# fan.net
KiCad netlist of a schematic drawn in EAGLE
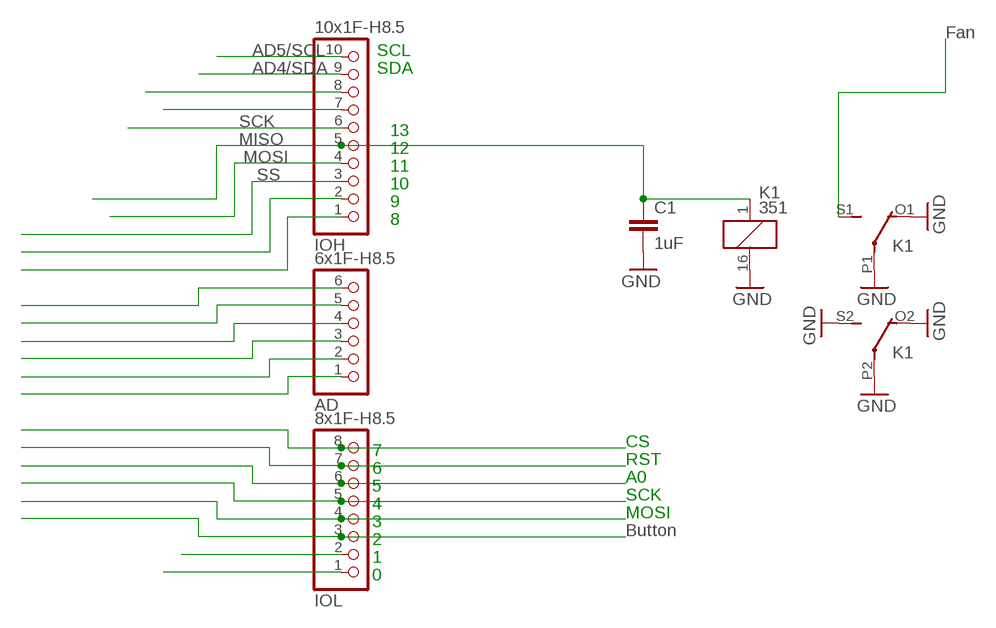
[diagram p0: schematic, sheet 1]

(export (version "E")
  (design (tool "Eeschema 10.0.6"))
  (components
    (comp (ref "AD")
      (value "6x1F-H8.5")
      (footprint "eagle-import:1X06")
      (libsource (lib "eagle-import") (part "PINHD-1X6"))
    )
    (comp (ref "C1")
      (value "1uF")
      (footprint "eagle-import:C2.5-3")
      (libsource (lib "eagle-import") (part "C2,5-3"))
    )
    (comp (ref "IOH")
      (value "10x1F-H8.5")
      (footprint "eagle-import:1X10")
      (libsource (lib "eagle-import") (part "PINHD-1X10_ARD"))
    )
    (comp (ref "IOL")
      (value "8x1F-H8.5")
      (footprint "eagle-import:1X08")
      (libsource (lib "eagle-import") (part "PINHD-1X8"))
    )
    (comp (ref "K1")
      (value "351")
      (footprint "eagle-import:351")
      (libsource (lib "eagle-import") (part "351"))
    )
  )
  (nets
    (net (code "1") (name "/AD4{slash}SDA") (class "Default")
      (node (ref "AD") (pin "5") (pinfunction "5_5") (pintype "passive"))
      (node (ref "IOH") (pin "9") (pinfunction "9_9") (pintype "passive"))
    )
    (net (code "2") (name "/AD5{slash}SCL") (class "Default")
      (node (ref "AD") (pin "6") (pinfunction "6_6") (pintype "passive"))
      (node (ref "IOH") (pin "10") (pinfunction "10_10") (pintype "passive"))
    )
    (net (code "3") (name "/MISO") (class "Default")
      (node (ref "C1") (pin "1") (pinfunction "1_1") (pintype "passive"))
      (node (ref "IOH") (pin "5") (pinfunction "5_5") (pintype "passive"))
      (node (ref "K1") (pin "1") (pinfunction "1_1") (pintype "passive"))
    )
    (net (code "4") (name "/MOSI") (class "Default")
      (node (ref "IOH") (pin "4") (pinfunction "4_4") (pintype "passive"))
    )
    (net (code "5") (name "/SCK") (class "Default")
      (node (ref "IOH") (pin "6") (pinfunction "6_6") (pintype "passive"))
    )
    (net (code "6") (name "/SS") (class "Default")
      (node (ref "IOH") (pin "3") (pinfunction "3_3") (pintype "passive"))
    )
    (net (code "7") (name "GND") (class "Default")
      (node (ref "C1") (pin "2") (pinfunction "2_2") (pintype "passive"))
      (node (ref "IOH") (pin "7") (pinfunction "7_7") (pintype "passive"))
      (node (ref "K1") (pin "16") (pinfunction "2_16") (pintype "passive"))
      (node (ref "K1") (pin "O1") (pinfunction "O_O1") (pintype "passive"))
      (node (ref "K1") (pin "O2") (pinfunction "O_O2") (pintype "passive"))
      (node (ref "K1") (pin "P1") (pinfunction "P_P1") (pintype "passive"))
      (node (ref "K1") (pin "P2") (pinfunction "P_P2") (pintype "passive"))
      (node (ref "K1") (pin "S2") (pinfunction "S_S2") (pintype "passive"))
    )
    (net (code "8") (name "unconnected-(AD-Pad1)") (class "Default")
      (node (ref "AD") (pin "1") (pinfunction "1_1") (pintype "passive"))
    )
    (net (code "9") (name "unconnected-(AD-Pad2)") (class "Default")
      (node (ref "AD") (pin "2") (pinfunction "2_2") (pintype "passive"))
    )
    (net (code "10") (name "unconnected-(AD-Pad3)") (class "Default")
      (node (ref "AD") (pin "3") (pinfunction "3_3") (pintype "passive"))
    )
    (net (code "11") (name "unconnected-(AD-Pad4)") (class "Default")
      (node (ref "AD") (pin "4") (pinfunction "4_4") (pintype "passive"))
    )
    (net (code "12") (name "unconnected-(IOH-Pad1)") (class "Default")
      (node (ref "IOH") (pin "1") (pinfunction "1_1") (pintype "passive"))
    )
    (net (code "13") (name "unconnected-(IOH-Pad2)") (class "Default")
      (node (ref "IOH") (pin "2") (pinfunction "2_2") (pintype "passive"))
    )
    (net (code "14") (name "unconnected-(IOH-Pad8)") (class "Default")
      (node (ref "IOH") (pin "8") (pinfunction "8_8") (pintype "passive"))
    )
    (net (code "15") (name "unconnected-(IOL-Pad1)") (class "Default")
      (node (ref "IOL") (pin "1") (pinfunction "1_1") (pintype "passive"))
    )
    (net (code "16") (name "unconnected-(IOL-Pad2)") (class "Default")
      (node (ref "IOL") (pin "2") (pinfunction "2_2") (pintype "passive"))
    )
    (net (code "17") (name "unconnected-(IOL-Pad3)") (class "Default")
      (node (ref "IOL") (pin "3") (pinfunction "3_3") (pintype "passive"))
    )
    (net (code "18") (name "unconnected-(IOL-Pad4)") (class "Default")
      (node (ref "IOL") (pin "4") (pinfunction "4_4") (pintype "passive"))
    )
    (net (code "19") (name "unconnected-(IOL-Pad5)") (class "Default")
      (node (ref "IOL") (pin "5") (pinfunction "5_5") (pintype "passive"))
    )
    (net (code "20") (name "unconnected-(IOL-Pad6)") (class "Default")
      (node (ref "IOL") (pin "6") (pinfunction "6_6") (pintype "passive"))
    )
    (net (code "21") (name "unconnected-(IOL-Pad7)") (class "Default")
      (node (ref "IOL") (pin "7") (pinfunction "7_7") (pintype "passive"))
    )
    (net (code "22") (name "unconnected-(IOL-Pad8)") (class "Default")
      (node (ref "IOL") (pin "8") (pinfunction "8_8") (pintype "passive"))
    )
    (net (code "23") (name "unconnected-(K1B-S-PadS1)") (class "Default")
      (node (ref "K1") (pin "S1") (pinfunction "S_S1") (pintype "passive"))
    )
  )
)
